# IFA_v1.net
KiCad netlist of a schematic drawn in EAGLE
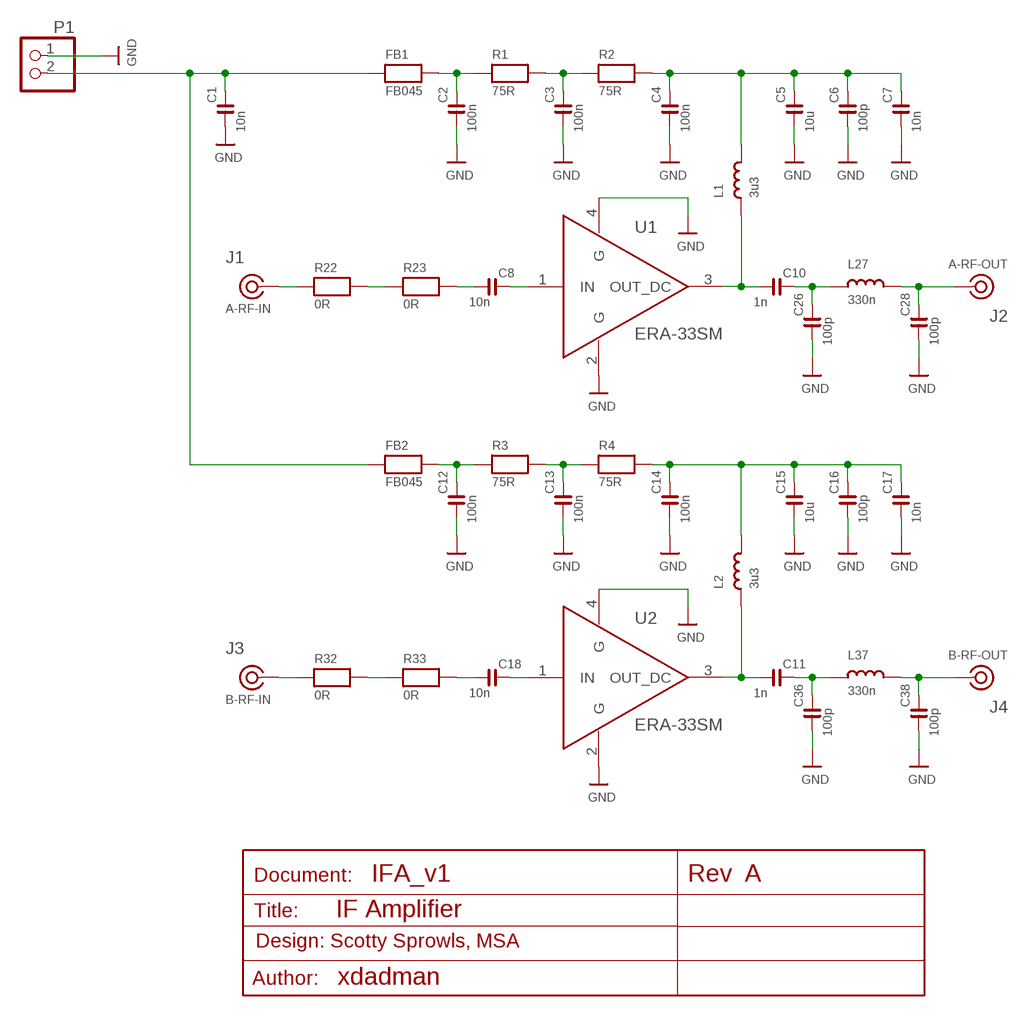
[diagram p0: schematic, sheet 1]

(export (version "E")
  (design (tool "Eeschema 10.0.6"))
  (components
    (comp (ref "C1")
      (value "10n")
      (footprint "eagle-import:C0805")
      (libsource (lib "eagle-import") (part "C080510N"))
    )
    (comp (ref "C2")
      (value "100n")
      (footprint "eagle-import:C0805")
      (libsource (lib "eagle-import") (part "C0805100N"))
    )
    (comp (ref "C3")
      (value "100n")
      (footprint "eagle-import:C0805")
      (libsource (lib "eagle-import") (part "C0805100N"))
    )
    (comp (ref "C4")
      (value "100n")
      (footprint "eagle-import:C0805")
      (libsource (lib "eagle-import") (part "C0805100N"))
    )
    (comp (ref "C5")
      (value "10u")
      (footprint "eagle-import:C1206")
      (libsource (lib "eagle-import") (part "CC120610U"))
    )
    (comp (ref "C6")
      (value "100p")
      (footprint "eagle-import:C0805")
      (libsource (lib "eagle-import") (part "C0805100P"))
    )
    (comp (ref "C7")
      (value "10n")
      (footprint "eagle-import:C0805")
      (libsource (lib "eagle-import") (part "C080510N"))
    )
    (comp (ref "C8")
      (value "10n")
      (footprint "eagle-import:C0805")
      (libsource (lib "eagle-import") (part "C080510N"))
    )
    (comp (ref "C10")
      (value "1n")
      (footprint "eagle-import:C0805")
      (libsource (lib "eagle-import") (part "C08051N"))
    )
    (comp (ref "C11")
      (value "1n")
      (footprint "eagle-import:C0805")
      (libsource (lib "eagle-import") (part "C08051N"))
    )
    (comp (ref "C12")
      (value "100n")
      (footprint "eagle-import:C0805")
      (libsource (lib "eagle-import") (part "C0805100N"))
    )
    (comp (ref "C13")
      (value "100n")
      (footprint "eagle-import:C0805")
      (libsource (lib "eagle-import") (part "C0805100N"))
    )
    (comp (ref "C14")
      (value "100n")
      (footprint "eagle-import:C0805")
      (libsource (lib "eagle-import") (part "C0805100N"))
    )
    (comp (ref "C15")
      (value "10u")
      (footprint "eagle-import:C1206")
      (libsource (lib "eagle-import") (part "CC120610U"))
    )
    (comp (ref "C16")
      (value "100p")
      (footprint "eagle-import:C0805")
      (libsource (lib "eagle-import") (part "C0805100P"))
    )
    (comp (ref "C17")
      (value "10n")
      (footprint "eagle-import:C0805")
      (libsource (lib "eagle-import") (part "C080510N"))
    )
    (comp (ref "C18")
      (value "10n")
      (footprint "eagle-import:C0805")
      (libsource (lib "eagle-import") (part "C080510N"))
    )
    (comp (ref "C26")
      (value "100p")
      (footprint "eagle-import:C0805")
      (libsource (lib "eagle-import") (part "C0805100P"))
    )
    (comp (ref "C28")
      (value "100p")
      (footprint "eagle-import:C0805")
      (libsource (lib "eagle-import") (part "C0805100P"))
    )
    (comp (ref "C36")
      (value "100p")
      (footprint "eagle-import:C0805")
      (libsource (lib "eagle-import") (part "C0805100P"))
    )
    (comp (ref "C38")
      (value "100p")
      (footprint "eagle-import:C0805")
      (libsource (lib "eagle-import") (part "C0805100P"))
    )
    (comp (ref "FB1")
      (value "FB045")
      (footprint "eagle-import:R0805")
      (libsource (lib "eagle-import") (part "R0805FB045"))
    )
    (comp (ref "FB2")
      (value "FB045")
      (footprint "eagle-import:R0805")
      (libsource (lib "eagle-import") (part "R0805FB045"))
    )
    (comp (ref "J1")
      (value "A-RF-IN")
      (footprint "eagle-import:SLIM_COAX_PAD")
      (libsource (lib "eagle-import") (part "COAX"))
    )
    (comp (ref "J2")
      (value "A-RF-OUT")
      (footprint "eagle-import:SLIM_COAX_PAD")
      (libsource (lib "eagle-import") (part "COAX"))
    )
    (comp (ref "J3")
      (value "B-RF-IN")
      (footprint "eagle-import:SLIM_COAX_PAD")
      (libsource (lib "eagle-import") (part "COAX"))
    )
    (comp (ref "J4")
      (value "B-RF-OUT")
      (footprint "eagle-import:SLIM_COAX_PAD")
      (libsource (lib "eagle-import") (part "COAX"))
    )
    (comp (ref "L1")
      (value "3u3")
      (footprint "eagle-import:L805")
      (libsource (lib "eagle-import") (part "L08053U3"))
    )
    (comp (ref "L2")
      (value "3u3")
      (footprint "eagle-import:L805")
      (libsource (lib "eagle-import") (part "L08053U3"))
    )
    (comp (ref "L27")
      (value "330n")
      (footprint "eagle-import:L805")
      (libsource (lib "eagle-import") (part "L0805330N"))
    )
    (comp (ref "L37")
      (value "330n")
      (footprint "eagle-import:L805")
      (libsource (lib "eagle-import") (part "L0805330N"))
    )
    (comp (ref "P1")
      (value "PINHD-1X2")
      (footprint "eagle-import:1X02")
      (libsource (lib "eagle-import") (part "PINHD-1X2"))
    )
    (comp (ref "R1")
      (value "75R")
      (footprint "eagle-import:R0805")
      (libsource (lib "eagle-import") (part "R080575R"))
    )
    (comp (ref "R2")
      (value "75R")
      (footprint "eagle-import:R0805")
      (libsource (lib "eagle-import") (part "R080575R"))
    )
    (comp (ref "R3")
      (value "75R")
      (footprint "eagle-import:R0805")
      (libsource (lib "eagle-import") (part "R080575R"))
    )
    (comp (ref "R4")
      (value "75R")
      (footprint "eagle-import:R0805")
      (libsource (lib "eagle-import") (part "R080575R"))
    )
    (comp (ref "R22")
      (value "0R")
      (footprint "eagle-import:R0805")
      (libsource (lib "eagle-import") (part "R08050R"))
    )
    (comp (ref "R23")
      (value "0R")
      (footprint "eagle-import:R0805")
      (libsource (lib "eagle-import") (part "R08050R"))
    )
    (comp (ref "R32")
      (value "0R")
      (footprint "eagle-import:R0805")
      (libsource (lib "eagle-import") (part "R08050R"))
    )
    (comp (ref "R33")
      (value "0R")
      (footprint "eagle-import:R0805")
      (libsource (lib "eagle-import") (part "R08050R"))
    )
    (comp (ref "U1")
      (value "ERA-33SM")
      (footprint "eagle-import:WW107")
      (libsource (lib "eagle-import") (part "ERA-33SM"))
    )
    (comp (ref "U2")
      (value "ERA-33SM")
      (footprint "eagle-import:WW107")
      (libsource (lib "eagle-import") (part "ERA-33SM"))
    )
  )
  (nets
    (net (code "1") (name "GND") (class "Default")
      (node (ref "C1") (pin "1") (pinfunction "1_1") (pintype "passive"))
      (node (ref "C12") (pin "1") (pinfunction "1_1") (pintype "passive"))
      (node (ref "C13") (pin "1") (pinfunction "1_1") (pintype "passive"))
      (node (ref "C14") (pin "1") (pinfunction "1_1") (pintype "passive"))
      (node (ref "C15") (pin "1") (pinfunction "1_1") (pintype "passive"))
      (node (ref "C16") (pin "1") (pinfunction "1_1") (pintype "passive"))
      (node (ref "C17") (pin "1") (pinfunction "1_1") (pintype "passive"))
      (node (ref "C2") (pin "1") (pinfunction "1_1") (pintype "passive"))
      (node (ref "C26") (pin "1") (pinfunction "1_1") (pintype "passive"))
      (node (ref "C28") (pin "1") (pinfunction "1_1") (pintype "passive"))
      (node (ref "C3") (pin "1") (pinfunction "1_1") (pintype "passive"))
      (node (ref "C36") (pin "1") (pinfunction "1_1") (pintype "passive"))
      (node (ref "C38") (pin "1") (pinfunction "1_1") (pintype "passive"))
      (node (ref "C4") (pin "1") (pinfunction "1_1") (pintype "passive"))
      (node (ref "C5") (pin "1") (pinfunction "1_1") (pintype "passive"))
      (node (ref "C6") (pin "1") (pinfunction "1_1") (pintype "passive"))
      (node (ref "C7") (pin "1") (pinfunction "1_1") (pintype "passive"))
      (node (ref "P1") (pin "1") (pinfunction "1_1") (pintype "passive"))
      (node (ref "U1") (pin "2") (pinfunction "G_2") (pintype "bidirectional"))
      (node (ref "U1") (pin "4") (pinfunction "G_4") (pintype "bidirectional"))
      (node (ref "U2") (pin "2") (pinfunction "G_2") (pintype "bidirectional"))
      (node (ref "U2") (pin "4") (pinfunction "G_4") (pintype "bidirectional"))
    )
    (net (code "2") (name "Net-(C1-Pad2)") (class "Default")
      (node (ref "C1") (pin "2") (pinfunction "2_2") (pintype "passive"))
      (node (ref "FB1") (pin "1") (pinfunction "1_1") (pintype "passive"))
      (node (ref "FB2") (pin "1") (pinfunction "1_1") (pintype "passive"))
      (node (ref "P1") (pin "2") (pinfunction "2_2") (pintype "passive"))
    )
    (net (code "3") (name "Net-(C2-Pad2)") (class "Default")
      (node (ref "C2") (pin "2") (pinfunction "2_2") (pintype "passive"))
      (node (ref "FB1") (pin "2") (pinfunction "2_2") (pintype "passive"))
      (node (ref "R1") (pin "1") (pinfunction "1_1") (pintype "passive"))
    )
    (net (code "4") (name "Net-(C3-Pad2)") (class "Default")
      (node (ref "C3") (pin "2") (pinfunction "2_2") (pintype "passive"))
      (node (ref "R1") (pin "2") (pinfunction "2_2") (pintype "passive"))
      (node (ref "R2") (pin "1") (pinfunction "1_1") (pintype "passive"))
    )
    (net (code "5") (name "Net-(C4-Pad2)") (class "Default")
      (node (ref "C4") (pin "2") (pinfunction "2_2") (pintype "passive"))
      (node (ref "C5") (pin "2") (pinfunction "2_2") (pintype "passive"))
      (node (ref "C6") (pin "2") (pinfunction "2_2") (pintype "passive"))
      (node (ref "C7") (pin "2") (pinfunction "2_2") (pintype "passive"))
      (node (ref "L1") (pin "2") (pinfunction "2_2") (pintype "passive"))
      (node (ref "R2") (pin "2") (pinfunction "2_2") (pintype "passive"))
    )
    (net (code "6") (name "Net-(C8-Pad1)") (class "Default")
      (node (ref "C8") (pin "1") (pinfunction "1_1") (pintype "passive"))
      (node (ref "R23") (pin "2") (pinfunction "2_2") (pintype "passive"))
    )
    (net (code "7") (name "Net-(C10-Pad2)") (class "Default")
      (node (ref "C10") (pin "2") (pinfunction "2_2") (pintype "passive"))
      (node (ref "C26") (pin "2") (pinfunction "2_2") (pintype "passive"))
      (node (ref "L27") (pin "1") (pinfunction "1_1") (pintype "passive"))
    )
    (net (code "8") (name "Net-(C11-Pad2)") (class "Default")
      (node (ref "C11") (pin "2") (pinfunction "2_2") (pintype "passive"))
      (node (ref "C36") (pin "2") (pinfunction "2_2") (pintype "passive"))
      (node (ref "L37") (pin "1") (pinfunction "1_1") (pintype "passive"))
    )
    (net (code "9") (name "Net-(C12-Pad2)") (class "Default")
      (node (ref "C12") (pin "2") (pinfunction "2_2") (pintype "passive"))
      (node (ref "FB2") (pin "2") (pinfunction "2_2") (pintype "passive"))
      (node (ref "R3") (pin "1") (pinfunction "1_1") (pintype "passive"))
    )
    (net (code "10") (name "Net-(C13-Pad2)") (class "Default")
      (node (ref "C13") (pin "2") (pinfunction "2_2") (pintype "passive"))
      (node (ref "R3") (pin "2") (pinfunction "2_2") (pintype "passive"))
      (node (ref "R4") (pin "1") (pinfunction "1_1") (pintype "passive"))
    )
    (net (code "11") (name "Net-(C14-Pad2)") (class "Default")
      (node (ref "C14") (pin "2") (pinfunction "2_2") (pintype "passive"))
      (node (ref "C15") (pin "2") (pinfunction "2_2") (pintype "passive"))
      (node (ref "C16") (pin "2") (pinfunction "2_2") (pintype "passive"))
      (node (ref "C17") (pin "2") (pinfunction "2_2") (pintype "passive"))
      (node (ref "L2") (pin "2") (pinfunction "2_2") (pintype "passive"))
      (node (ref "R4") (pin "2") (pinfunction "2_2") (pintype "passive"))
    )
    (net (code "12") (name "Net-(C18-Pad1)") (class "Default")
      (node (ref "C18") (pin "1") (pinfunction "1_1") (pintype "passive"))
      (node (ref "R33") (pin "2") (pinfunction "2_2") (pintype "passive"))
    )
    (net (code "13") (name "Net-(J1A-1)") (class "Default")
      (node (ref "J1") (pin "SIG") (pinfunction "1_SIG") (pintype "passive"))
      (node (ref "R22") (pin "1") (pinfunction "1_1") (pintype "passive"))
    )
    (net (code "14") (name "Net-(J2A-1)") (class "Default")
      (node (ref "C28") (pin "2") (pinfunction "2_2") (pintype "passive"))
      (node (ref "J2") (pin "SIG") (pinfunction "1_SIG") (pintype "passive"))
      (node (ref "L27") (pin "2") (pinfunction "2_2") (pintype "passive"))
    )
    (net (code "15") (name "Net-(J3A-1)") (class "Default")
      (node (ref "J3") (pin "SIG") (pinfunction "1_SIG") (pintype "passive"))
      (node (ref "R32") (pin "1") (pinfunction "1_1") (pintype "passive"))
    )
    (net (code "16") (name "Net-(J4A-1)") (class "Default")
      (node (ref "C38") (pin "2") (pinfunction "2_2") (pintype "passive"))
      (node (ref "J4") (pin "SIG") (pinfunction "1_SIG") (pintype "passive"))
      (node (ref "L37") (pin "2") (pinfunction "2_2") (pintype "passive"))
    )
    (net (code "17") (name "Net-(R22-Pad2)") (class "Default")
      (node (ref "R22") (pin "2") (pinfunction "2_2") (pintype "passive"))
      (node (ref "R23") (pin "1") (pinfunction "1_1") (pintype "passive"))
    )
    (net (code "18") (name "Net-(R32-Pad2)") (class "Default")
      (node (ref "R32") (pin "2") (pinfunction "2_2") (pintype "passive"))
      (node (ref "R33") (pin "1") (pinfunction "1_1") (pintype "passive"))
    )
    (net (code "19") (name "Net-(U1-IN)") (class "Default")
      (node (ref "C8") (pin "2") (pinfunction "2_2") (pintype "passive"))
      (node (ref "U1") (pin "1") (pinfunction "IN_1") (pintype "bidirectional"))
    )
    (net (code "20") (name "Net-(U1-OUT_DC)") (class "Default")
      (node (ref "C10") (pin "1") (pinfunction "1_1") (pintype "passive"))
      (node (ref "L1") (pin "1") (pinfunction "1_1") (pintype "passive"))
      (node (ref "U1") (pin "3") (pinfunction "OUT_DC_3") (pintype "bidirectional"))
    )
    (net (code "21") (name "Net-(U2-IN)") (class "Default")
      (node (ref "C18") (pin "2") (pinfunction "2_2") (pintype "passive"))
      (node (ref "U2") (pin "1") (pinfunction "IN_1") (pintype "bidirectional"))
    )
    (net (code "22") (name "Net-(U2-OUT_DC)") (class "Default")
      (node (ref "C11") (pin "1") (pinfunction "1_1") (pintype "passive"))
      (node (ref "L2") (pin "1") (pinfunction "1_1") (pintype "passive"))
      (node (ref "U2") (pin "3") (pinfunction "OUT_DC_3") (pintype "bidirectional"))
    )
  )
)
